# decoder.net
KiCad netlist of a schematic drawn in EAGLE
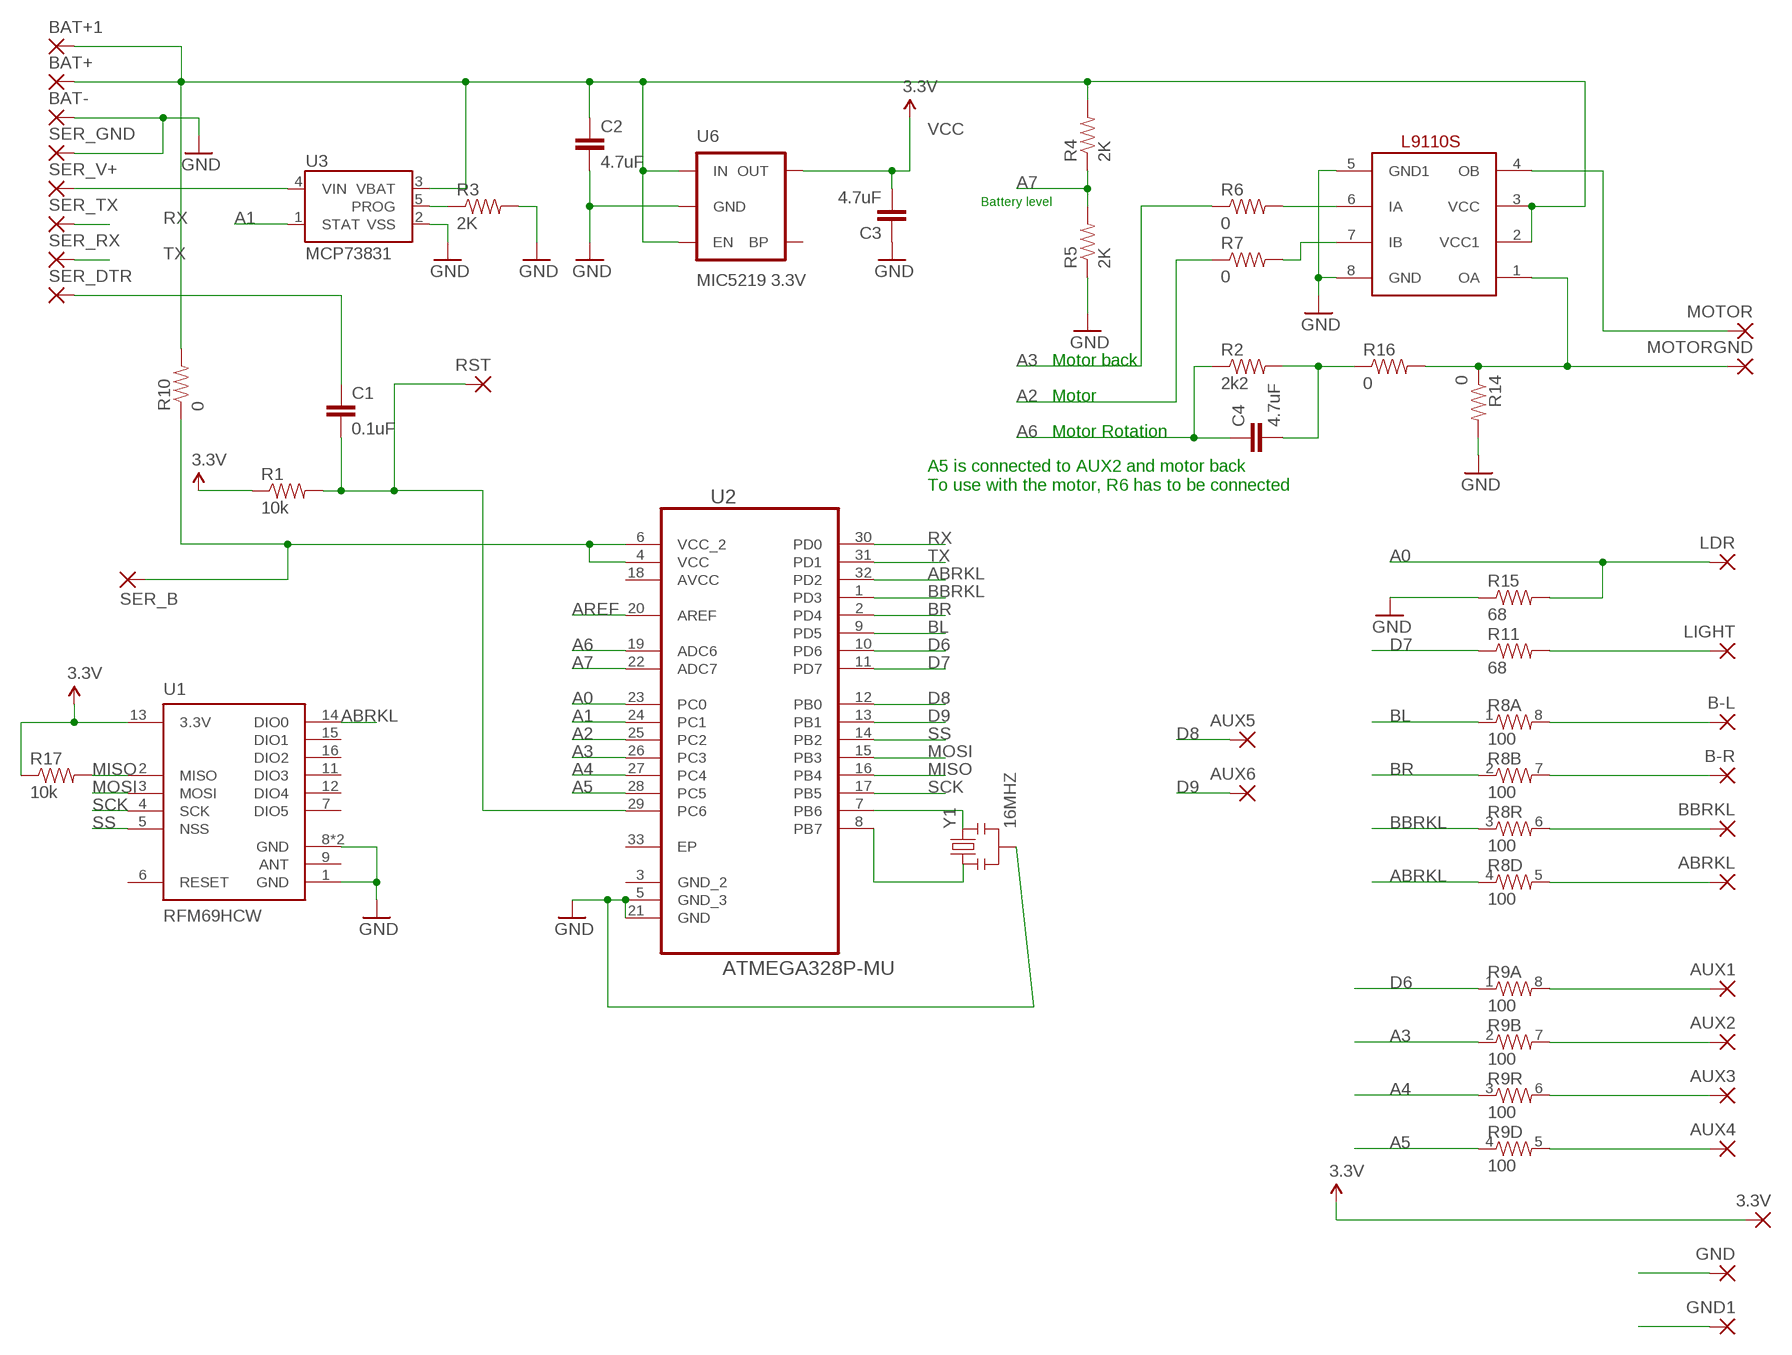
[diagram p0: schematic, sheet 1]

(export (version "E")
  (design (tool "Eeschema 10.0.6"))
  (components
    (comp (ref "3.3V")
      (value "SMD2")
      (footprint "eagle-import:SMD1,27-2,54")
      (libsource (lib "eagle-import") (part "SMD2"))
    )
    (comp (ref "ABRKL")
      (value "SMD2")
      (footprint "eagle-import:SMD1,27-2,54")
      (libsource (lib "eagle-import") (part "SMD2"))
    )
    (comp (ref "AUX1")
      (value "SMD2")
      (footprint "eagle-import:SMD1,27-2,54")
      (libsource (lib "eagle-import") (part "SMD2"))
    )
    (comp (ref "AUX2")
      (value "SMD2")
      (footprint "eagle-import:SMD1,27-2,54")
      (libsource (lib "eagle-import") (part "SMD2"))
    )
    (comp (ref "AUX3")
      (value "SMD2")
      (footprint "eagle-import:SMD1,27-2,54")
      (libsource (lib "eagle-import") (part "SMD2"))
    )
    (comp (ref "AUX4")
      (value "SMD2")
      (footprint "eagle-import:SMD1,27-2,54")
      (libsource (lib "eagle-import") (part "SMD2"))
    )
    (comp (ref "AUX5")
      (value "SMD2")
      (footprint "eagle-import:SMD1,27-2,54")
      (libsource (lib "eagle-import") (part "SMD2"))
    )
    (comp (ref "AUX6")
      (value "SMD2")
      (footprint "eagle-import:SMD1,27-2,54")
      (libsource (lib "eagle-import") (part "SMD2"))
    )
    (comp (ref "B-L")
      (value "SMD2")
      (footprint "eagle-import:SMD1,27-2,54")
      (libsource (lib "eagle-import") (part "SMD2"))
    )
    (comp (ref "B-R")
      (value "SMD2")
      (footprint "eagle-import:SMD1,27-2,54")
      (libsource (lib "eagle-import") (part "SMD2"))
    )
    (comp (ref "BAT+")
      (value "SMD2")
      (footprint "eagle-import:SMD1,27-2,54")
      (libsource (lib "eagle-import") (part "SMD2"))
    )
    (comp (ref "BAT+1")
      (value "SMD2")
      (footprint "eagle-import:SMD1,27-2,54")
      (libsource (lib "eagle-import") (part "SMD2"))
    )
    (comp (ref "BAT-")
      (value "SMD2")
      (footprint "eagle-import:SMD1,27-2,54")
      (libsource (lib "eagle-import") (part "SMD2"))
    )
    (comp (ref "BBRKL")
      (value "SMD2")
      (footprint "eagle-import:SMD1,27-2,54")
      (libsource (lib "eagle-import") (part "SMD2"))
    )
    (comp (ref "C1")
      (value "0.1uF")
      (footprint "eagle-import:0805")
      (libsource (lib "eagle-import") (part "CAP0805"))
    )
    (comp (ref "C2")
      (value "4.7uF")
      (footprint "eagle-import:0805")
      (libsource (lib "eagle-import") (part "CAP0805"))
    )
    (comp (ref "C3")
      (value "4.7uF")
      (footprint "eagle-import:0805")
      (libsource (lib "eagle-import") (part "CAP0805"))
    )
    (comp (ref "C4")
      (value "4.7uF")
      (footprint "eagle-import:0805")
      (libsource (lib "eagle-import") (part "CAP0805"))
    )
    (comp (ref "GND")
      (value "SMD2")
      (footprint "eagle-import:SMD1,27-2,54")
      (libsource (lib "eagle-import") (part "SMD2"))
    )
    (comp (ref "GND1")
      (value "SMD2")
      (footprint "eagle-import:SMD1,27-2,54")
      (libsource (lib "eagle-import") (part "SMD2"))
    )
    (comp (ref "LDR")
      (value "SMD2")
      (footprint "eagle-import:SMD1,27-2,54")
      (libsource (lib "eagle-import") (part "SMD2"))
    )
    (comp (ref "LIGHT")
      (value "SMD2")
      (footprint "eagle-import:SMD1,27-2,54")
      (libsource (lib "eagle-import") (part "SMD2"))
    )
    (comp (ref "MDRIVER")
      (value "L9110S")
      (footprint "eagle-import:SO08")
      (libsource (lib "eagle-import") (part "L9110S"))
    )
    (comp (ref "MOTOR")
      (value "SMD2")
      (footprint "eagle-import:SMD1,27-2,54")
      (libsource (lib "eagle-import") (part "SMD2"))
    )
    (comp (ref "MOTORGND")
      (value "SMD2")
      (footprint "eagle-import:SMD1,27-2,54")
      (libsource (lib "eagle-import") (part "SMD2"))
    )
    (comp (ref "R1")
      (value "10k")
      (footprint "eagle-import:0603-RES")
      (libsource (lib "eagle-import") (part "RESISTOR0603-RES"))
    )
    (comp (ref "R2")
      (value "2k2")
      (footprint "eagle-import:0603-RES")
      (libsource (lib "eagle-import") (part "RESISTOR0603-RES"))
    )
    (comp (ref "R3")
      (value "2K")
      (footprint "eagle-import:0603-RES")
      (libsource (lib "eagle-import") (part "RESISTOR0603-RES"))
    )
    (comp (ref "R4")
      (value "2K")
      (footprint "eagle-import:0603-RES")
      (libsource (lib "eagle-import") (part "RESISTOR0603-RES"))
    )
    (comp (ref "R5")
      (value "2K")
      (footprint "eagle-import:0603-RES")
      (libsource (lib "eagle-import") (part "RESISTOR0603-RES"))
    )
    (comp (ref "R6")
      (value "0")
      (footprint "eagle-import:0603-RES")
      (libsource (lib "eagle-import") (part "RESISTOR0603-RES"))
    )
    (comp (ref "R7")
      (value "0")
      (footprint "eagle-import:0603-RES")
      (libsource (lib "eagle-import") (part "RESISTOR0603-RES"))
    )
    (comp (ref "R8")
      (value "100")
      (footprint "eagle-import:0603-ARV")
      (libsource (lib "eagle-import") (part "RESISTOR-ARRAY0603-ARV"))
    )
    (comp (ref "R9")
      (value "100")
      (footprint "eagle-import:0603-ARV")
      (libsource (lib "eagle-import") (part "RESISTOR-ARRAY0603-ARV"))
    )
    (comp (ref "R10")
      (value "0")
      (footprint "eagle-import:0603-RES")
      (libsource (lib "eagle-import") (part "RESISTOR0603-RES"))
    )
    (comp (ref "R11")
      (value "68")
      (footprint "eagle-import:0603-RES")
      (libsource (lib "eagle-import") (part "RESISTOR0603-RES"))
    )
    (comp (ref "R14")
      (value "0")
      (footprint "eagle-import:0603-RES")
      (libsource (lib "eagle-import") (part "RESISTOR0603-RES"))
    )
    (comp (ref "R15")
      (value "68")
      (footprint "eagle-import:0603-RES")
      (libsource (lib "eagle-import") (part "RESISTOR0603-RES"))
    )
    (comp (ref "R16")
      (value "0")
      (footprint "eagle-import:0603-RES")
      (libsource (lib "eagle-import") (part "RESISTOR0603-RES"))
    )
    (comp (ref "R17")
      (value "10k")
      (footprint "eagle-import:0603-RES")
      (libsource (lib "eagle-import") (part "RESISTOR0603-RES"))
    )
    (comp (ref "RST")
      (value "SMD2")
      (footprint "eagle-import:SMD1,27-2,54")
      (libsource (lib "eagle-import") (part "SMD2"))
    )
    (comp (ref "SER_B")
      (value "SMD2")
      (footprint "eagle-import:SMD1,27-2,54")
      (libsource (lib "eagle-import") (part "SMD2"))
    )
    (comp (ref "SER_DTR")
      (value "SMD2")
      (footprint "eagle-import:SMD1,27-2,54")
      (libsource (lib "eagle-import") (part "SMD2"))
    )
    (comp (ref "SER_GND")
      (value "SMD2")
      (footprint "eagle-import:SMD1,27-2,54")
      (libsource (lib "eagle-import") (part "SMD2"))
    )
    (comp (ref "SER_RX")
      (value "SMD2")
      (footprint "eagle-import:SMD1,27-2,54")
      (libsource (lib "eagle-import") (part "SMD2"))
    )
    (comp (ref "SER_TX")
      (value "SMD2")
      (footprint "eagle-import:SMD1,27-2,54")
      (libsource (lib "eagle-import") (part "SMD2"))
    )
    (comp (ref "SER_V+")
      (value "SMD2")
      (footprint "eagle-import:SMD1,27-2,54")
      (libsource (lib "eagle-import") (part "SMD2"))
    )
    (comp (ref "U1")
      (value "RFM69HCW")
      (footprint "eagle-import:RFM69HCW-XXXS2")
      (libsource (lib "eagle-import") (part "RFM69HCW"))
    )
    (comp (ref "U2")
      (value "ATMEGA328P-MU")
      (footprint "eagle-import:QFN50P500X500X100-33N")
      (libsource (lib "eagle-import") (part "ATMEGA328P-MU"))
    )
    (comp (ref "U3")
      (value "MCP73831")
      (footprint "eagle-import:SOT23-5")
      (libsource (lib "eagle-import") (part "MCP73831"))
    )
    (comp (ref "U6")
      (value "MIC5219 3.3V")
      (footprint "eagle-import:SOT23-5")
      (libsource (lib "eagle-import") (part "V_REG_MIC52193.3V"))
    )
    (comp (ref "Y1")
      (value "16MHZ")
      (footprint "eagle-import:RESONATOR-SMD")
      (libsource (lib "eagle-import") (part "RESONATOR16MHZ"))
    )
  )
  (nets
    (net (code "1") (name "/A0") (class "Default")
      (node (ref "LDR") (pin "1") (pinfunction "P_1") (pintype "passive"))
      (node (ref "R15") (pin "2") (pinfunction "2_2") (pintype "passive"))
      (node (ref "U2") (pin "23") (pinfunction "PC0_23") (pintype "bidirectional"))
    )
    (net (code "2") (name "/A1") (class "Default")
      (node (ref "U2") (pin "24") (pinfunction "PC1_24") (pintype "bidirectional"))
      (node (ref "U3") (pin "1") (pinfunction "STAT_1") (pintype "output"))
    )
    (net (code "3") (name "/A2") (class "Default")
      (node (ref "R7") (pin "1") (pinfunction "1_1") (pintype "passive"))
      (node (ref "U2") (pin "25") (pinfunction "PC2_25") (pintype "bidirectional"))
    )
    (net (code "4") (name "/A3") (class "Default")
      (node (ref "R6") (pin "1") (pinfunction "1_1") (pintype "passive"))
      (node (ref "R9") (pin "2") (pinfunction "1_2") (pintype "passive"))
      (node (ref "U2") (pin "26") (pinfunction "PC3_26") (pintype "bidirectional"))
    )
    (net (code "5") (name "/A4") (class "Default")
      (node (ref "R9") (pin "3") (pinfunction "1_3") (pintype "passive"))
      (node (ref "U2") (pin "27") (pinfunction "PC4_27") (pintype "bidirectional"))
    )
    (net (code "6") (name "/A5") (class "Default")
      (node (ref "R9") (pin "4") (pinfunction "1_4") (pintype "passive"))
      (node (ref "U2") (pin "28") (pinfunction "PC5_28") (pintype "bidirectional"))
    )
    (net (code "7") (name "/A6") (class "Default")
      (node (ref "C4") (pin "1") (pinfunction "1_1") (pintype "passive"))
      (node (ref "R2") (pin "1") (pinfunction "1_1") (pintype "passive"))
      (node (ref "U2") (pin "19") (pinfunction "ADC6_19") (pintype "input"))
    )
    (net (code "8") (name "/A7") (class "Default")
      (node (ref "R4") (pin "1") (pinfunction "1_1") (pintype "passive"))
      (node (ref "R5") (pin "2") (pinfunction "2_2") (pintype "passive"))
      (node (ref "U2") (pin "22") (pinfunction "ADC7_22") (pintype "input"))
    )
    (net (code "9") (name "/ABRKL") (class "Default")
      (node (ref "R8") (pin "4") (pinfunction "1_4") (pintype "passive"))
      (node (ref "U1") (pin "14") (pinfunction "DIO0_14") (pintype "bidirectional"))
      (node (ref "U2") (pin "32") (pinfunction "PD2_32") (pintype "bidirectional"))
    )
    (net (code "10") (name "/AREF") (class "Default")
      (node (ref "U2") (pin "20") (pinfunction "AREF_20") (pintype "input"))
    )
    (net (code "11") (name "/AVCC") (class "Default")
      (node (ref "U2") (pin "18") (pinfunction "AVCC_18") (pintype "power_in"))
    )
    (net (code "12") (name "/BBRKL") (class "Default")
      (node (ref "R8") (pin "3") (pinfunction "1_3") (pintype "passive"))
      (node (ref "U2") (pin "1") (pinfunction "PD3_1") (pintype "bidirectional"))
    )
    (net (code "13") (name "/BL") (class "Default")
      (node (ref "R8") (pin "1") (pinfunction "1_1") (pintype "passive"))
      (node (ref "U2") (pin "9") (pinfunction "PD5_9") (pintype "bidirectional"))
    )
    (net (code "14") (name "/BR") (class "Default")
      (node (ref "R8") (pin "2") (pinfunction "1_2") (pintype "passive"))
      (node (ref "U2") (pin "2") (pinfunction "PD4_2") (pintype "bidirectional"))
    )
    (net (code "15") (name "/D6") (class "Default")
      (node (ref "R9") (pin "1") (pinfunction "1_1") (pintype "passive"))
      (node (ref "U2") (pin "10") (pinfunction "PD6_10") (pintype "bidirectional"))
    )
    (net (code "16") (name "/D7") (class "Default")
      (node (ref "R11") (pin "1") (pinfunction "1_1") (pintype "passive"))
      (node (ref "U2") (pin "11") (pinfunction "PD7_11") (pintype "bidirectional"))
    )
    (net (code "17") (name "/D8") (class "Default")
      (node (ref "AUX5") (pin "1") (pinfunction "P_1") (pintype "passive"))
      (node (ref "U2") (pin "12") (pinfunction "PB0_12") (pintype "bidirectional"))
    )
    (net (code "18") (name "/D9") (class "Default")
      (node (ref "AUX6") (pin "1") (pinfunction "P_1") (pintype "passive"))
      (node (ref "U2") (pin "13") (pinfunction "PB1_13") (pintype "bidirectional"))
    )
    (net (code "19") (name "/MISO") (class "Default")
      (node (ref "R17") (pin "2") (pinfunction "2_2") (pintype "passive"))
      (node (ref "U1") (pin "2") (pinfunction "MISO_2") (pintype "bidirectional"))
      (node (ref "U2") (pin "16") (pinfunction "PB4_16") (pintype "bidirectional"))
    )
    (net (code "20") (name "/MOSI") (class "Default")
      (node (ref "U1") (pin "3") (pinfunction "MOSI_3") (pintype "input"))
      (node (ref "U2") (pin "15") (pinfunction "PB3_15") (pintype "bidirectional"))
    )
    (net (code "21") (name "/RX") (class "Default")
      (node (ref "SER_TX") (pin "1") (pinfunction "P_1") (pintype "passive"))
      (node (ref "U2") (pin "30") (pinfunction "PD0_30") (pintype "bidirectional"))
    )
    (net (code "22") (name "/SCK") (class "Default")
      (node (ref "U1") (pin "4") (pinfunction "SCK_4") (pintype "input"))
      (node (ref "U2") (pin "17") (pinfunction "PB5_17") (pintype "bidirectional"))
    )
    (net (code "23") (name "/SS") (class "Default")
      (node (ref "U1") (pin "5") (pinfunction "NSS_5") (pintype "input"))
      (node (ref "U2") (pin "14") (pinfunction "PB2_14") (pintype "bidirectional"))
    )
    (net (code "24") (name "/TX") (class "Default")
      (node (ref "SER_RX") (pin "1") (pinfunction "P_1") (pintype "passive"))
      (node (ref "U2") (pin "31") (pinfunction "PD1_31") (pintype "bidirectional"))
    )
    (net (code "25") (name "3.3V") (class "Default")
      (node (ref "3.3V") (pin "1") (pinfunction "P_1") (pintype "passive"))
      (node (ref "C3") (pin "2") (pinfunction "2_2") (pintype "passive"))
      (node (ref "R1") (pin "1") (pinfunction "1_1") (pintype "passive"))
      (node (ref "R17") (pin "1") (pinfunction "1_1") (pintype "passive"))
      (node (ref "U1") (pin "13") (pinfunction "3.3V_13") (pintype "power_in"))
      (node (ref "U6") (pin "5") (pinfunction "OUT_5") (pintype "passive"))
    )
    (net (code "26") (name "GND") (class "Default")
      (node (ref "BAT-") (pin "1") (pinfunction "P_1") (pintype "passive"))
      (node (ref "C2") (pin "2") (pinfunction "2_2") (pintype "passive"))
      (node (ref "C3") (pin "1") (pinfunction "1_1") (pintype "passive"))
      (node (ref "GND") (pin "1") (pinfunction "P_1") (pintype "passive"))
      (node (ref "GND1") (pin "1") (pinfunction "P_1") (pintype "passive"))
      (node (ref "MDRIVER") (pin "5") (pinfunction "GND1_5") (pintype "passive"))
      (node (ref "MDRIVER") (pin "8") (pinfunction "GND_8") (pintype "output"))
      (node (ref "R14") (pin "2") (pinfunction "2_2") (pintype "passive"))
      (node (ref "R15") (pin "1") (pinfunction "1_1") (pintype "passive"))
      (node (ref "R3") (pin "2") (pinfunction "2_2") (pintype "passive"))
      (node (ref "R5") (pin "1") (pinfunction "1_1") (pintype "passive"))
      (node (ref "SER_GND") (pin "1") (pinfunction "P_1") (pintype "passive"))
      (node (ref "U1") (pin "1") (pinfunction "GND_1") (pintype "power_in"))
      (node (ref "U1") (pin "10") (pinfunction "GND_10") (pintype "power_in"))
      (node (ref "U1") (pin "8") (pinfunction "GND_8") (pintype "power_in"))
      (node (ref "U2") (pin "21") (pinfunction "GND_21") (pintype "passive"))
      (node (ref "U2") (pin "5") (pinfunction "GND_3_5") (pintype "passive"))
      (node (ref "U3") (pin "2") (pinfunction "VSS_2") (pintype "power_in"))
      (node (ref "U6") (pin "2") (pinfunction "GND_2") (pintype "input"))
      (node (ref "Y1") (pin "2") (pinfunction "2_2") (pintype "passive"))
    )
    (net (code "27") (name "Net-(ABRKL-P)") (class "Default")
      (node (ref "ABRKL") (pin "1") (pinfunction "P_1") (pintype "passive"))
      (node (ref "R8") (pin "5") (pinfunction "2_5") (pintype "passive"))
    )
    (net (code "28") (name "Net-(AUX1-P)") (class "Default")
      (node (ref "AUX1") (pin "1") (pinfunction "P_1") (pintype "passive"))
      (node (ref "R9") (pin "8") (pinfunction "2_8") (pintype "passive"))
    )
    (net (code "29") (name "Net-(AUX2-P)") (class "Default")
      (node (ref "AUX2") (pin "1") (pinfunction "P_1") (pintype "passive"))
      (node (ref "R9") (pin "7") (pinfunction "2_7") (pintype "passive"))
    )
    (net (code "30") (name "Net-(AUX3-P)") (class "Default")
      (node (ref "AUX3") (pin "1") (pinfunction "P_1") (pintype "passive"))
      (node (ref "R9") (pin "6") (pinfunction "2_6") (pintype "passive"))
    )
    (net (code "31") (name "Net-(AUX4-P)") (class "Default")
      (node (ref "AUX4") (pin "1") (pinfunction "P_1") (pintype "passive"))
      (node (ref "R9") (pin "5") (pinfunction "2_5") (pintype "passive"))
    )
    (net (code "32") (name "Net-(B-L-P)") (class "Default")
      (node (ref "B-L") (pin "1") (pinfunction "P_1") (pintype "passive"))
      (node (ref "R8") (pin "8") (pinfunction "2_8") (pintype "passive"))
    )
    (net (code "33") (name "Net-(B-R-P)") (class "Default")
      (node (ref "B-R") (pin "1") (pinfunction "P_1") (pintype "passive"))
      (node (ref "R8") (pin "7") (pinfunction "2_7") (pintype "passive"))
    )
    (net (code "34") (name "Net-(BAT+-P)") (class "Default")
      (node (ref "BAT+") (pin "1") (pinfunction "P_1") (pintype "passive"))
      (node (ref "BAT+1") (pin "1") (pinfunction "P_1") (pintype "passive"))
      (node (ref "C2") (pin "1") (pinfunction "1_1") (pintype "passive"))
      (node (ref "MDRIVER") (pin "2") (pinfunction "VCC1_2") (pintype "input"))
      (node (ref "MDRIVER") (pin "3") (pinfunction "VCC_3") (pintype "input"))
      (node (ref "R10") (pin "2") (pinfunction "2_2") (pintype "passive"))
      (node (ref "R4") (pin "2") (pinfunction "2_2") (pintype "passive"))
      (node (ref "U3") (pin "3") (pinfunction "VBAT_3") (pintype "power_in"))
      (node (ref "U6") (pin "1") (pinfunction "IN_1") (pintype "input"))
      (node (ref "U6") (pin "3") (pinfunction "EN_3") (pintype "input"))
    )
    (net (code "35") (name "Net-(BBRKL-P)") (class "Default")
      (node (ref "BBRKL") (pin "1") (pinfunction "P_1") (pintype "passive"))
      (node (ref "R8") (pin "6") (pinfunction "2_6") (pintype "passive"))
    )
    (net (code "36") (name "Net-(C4-Pad2)") (class "Default")
      (node (ref "C4") (pin "2") (pinfunction "2_2") (pintype "passive"))
      (node (ref "R16") (pin "1") (pinfunction "1_1") (pintype "passive"))
      (node (ref "R2") (pin "2") (pinfunction "2_2") (pintype "passive"))
    )
    (net (code "37") (name "Net-(LIGHT-P)") (class "Default")
      (node (ref "LIGHT") (pin "1") (pinfunction "P_1") (pintype "passive"))
      (node (ref "R11") (pin "2") (pinfunction "2_2") (pintype "passive"))
    )
    (net (code "38") (name "Net-(MDRIVER-IA)") (class "Default")
      (node (ref "MDRIVER") (pin "6") (pinfunction "IA_6") (pintype "passive"))
      (node (ref "R6") (pin "2") (pinfunction "2_2") (pintype "passive"))
    )
    (net (code "39") (name "Net-(MDRIVER-IB)") (class "Default")
      (node (ref "MDRIVER") (pin "7") (pinfunction "IB_7") (pintype "output"))
      (node (ref "R7") (pin "2") (pinfunction "2_2") (pintype "passive"))
    )
    (net (code "40") (name "Net-(MDRIVER-OA)") (class "Default")
      (node (ref "MDRIVER") (pin "1") (pinfunction "OA_1") (pintype "power_in"))
      (node (ref "MOTORGND") (pin "1") (pinfunction "P_1") (pintype "passive"))
      (node (ref "R14") (pin "1") (pinfunction "1_1") (pintype "passive"))
      (node (ref "R16") (pin "2") (pinfunction "2_2") (pintype "passive"))
    )
    (net (code "41") (name "Net-(MDRIVER-OB)") (class "Default")
      (node (ref "MDRIVER") (pin "4") (pinfunction "OB_4") (pintype "power_in"))
      (node (ref "MOTOR") (pin "1") (pinfunction "P_1") (pintype "passive"))
    )
    (net (code "42") (name "Net-(RST-P)") (class "Default")
      (node (ref "C1") (pin "2") (pinfunction "2_2") (pintype "passive"))
      (node (ref "R1") (pin "2") (pinfunction "2_2") (pintype "passive"))
      (node (ref "RST") (pin "1") (pinfunction "P_1") (pintype "passive"))
      (node (ref "U2") (pin "29") (pinfunction "PC6_29") (pintype "bidirectional"))
    )
    (net (code "43") (name "Net-(SER_B-P)") (class "Default")
      (node (ref "R10") (pin "1") (pinfunction "1_1") (pintype "passive"))
      (node (ref "SER_B") (pin "1") (pinfunction "P_1") (pintype "passive"))
      (node (ref "U2") (pin "4") (pinfunction "VCC_4") (pintype "power_in"))
      (node (ref "U2") (pin "6") (pinfunction "VCC_2_6") (pintype "power_in"))
    )
    (net (code "44") (name "Net-(SER_DTR-P)") (class "Default")
      (node (ref "C1") (pin "1") (pinfunction "1_1") (pintype "passive"))
      (node (ref "SER_DTR") (pin "1") (pinfunction "P_1") (pintype "passive"))
    )
    (net (code "45") (name "Net-(SER_V+-P)") (class "Default")
      (node (ref "SER_V+") (pin "1") (pinfunction "P_1") (pintype "passive"))
      (node (ref "U3") (pin "4") (pinfunction "VIN_4") (pintype "power_in"))
    )
    (net (code "46") (name "Net-(U2-PB6)") (class "Default")
      (node (ref "U2") (pin "7") (pinfunction "PB6_7") (pintype "bidirectional"))
      (node (ref "Y1") (pin "3") (pinfunction "3_3") (pintype "passive"))
    )
    (net (code "47") (name "Net-(U2-PB7)") (class "Default")
      (node (ref "U2") (pin "8") (pinfunction "PB7_8") (pintype "bidirectional"))
      (node (ref "Y1") (pin "1") (pinfunction "1_1") (pintype "passive"))
    )
    (net (code "48") (name "Net-(U3-PROG)") (class "Default")
      (node (ref "R3") (pin "1") (pinfunction "1_1") (pintype "passive"))
      (node (ref "U3") (pin "5") (pinfunction "PROG_5") (pintype "input"))
    )
    (net (code "49") (name "unconnected-(U1-ANT-Pad9)") (class "Default")
      (node (ref "U1") (pin "9") (pinfunction "ANT_9") (pintype "passive"))
    )
    (net (code "50") (name "unconnected-(U1-DIO1-Pad15)") (class "Default")
      (node (ref "U1") (pin "15") (pinfunction "DIO1_15") (pintype "bidirectional"))
    )
    (net (code "51") (name "unconnected-(U1-DIO2-Pad16)") (class "Default")
      (node (ref "U1") (pin "16") (pinfunction "DIO2_16") (pintype "bidirectional"))
    )
    (net (code "52") (name "unconnected-(U1-DIO3-Pad11)") (class "Default")
      (node (ref "U1") (pin "11") (pinfunction "DIO3_11") (pintype "bidirectional"))
    )
    (net (code "53") (name "unconnected-(U1-DIO4-Pad12)") (class "Default")
      (node (ref "U1") (pin "12") (pinfunction "DIO4_12") (pintype "bidirectional"))
    )
    (net (code "54") (name "unconnected-(U1-DIO5-Pad7)") (class "Default")
      (node (ref "U1") (pin "7") (pinfunction "DIO5_7") (pintype "bidirectional"))
    )
    (net (code "55") (name "unconnected-(U1-RESET-Pad6)") (class "Default")
      (node (ref "U1") (pin "6") (pinfunction "RESET_6") (pintype "input"))
    )
    (net (code "56") (name "unconnected-(U2-EP-Pad33)") (class "Default")
      (node (ref "U2") (pin "33") (pinfunction "EP_33") (pintype "passive"))
    )
    (net (code "57") (name "unconnected-(U2-GND_2-Pad3)") (class "Default")
      (node (ref "U2") (pin "3") (pinfunction "GND_2_3") (pintype "passive"))
    )
    (net (code "58") (name "unconnected-(U6-BP-Pad4)") (class "Default")
      (node (ref "U6") (pin "4") (pinfunction "BP_4") (pintype "input"))
    )
  )
)
